# Probe1152A.net
KiCad netlist of a schematic drawn in Altium Designer
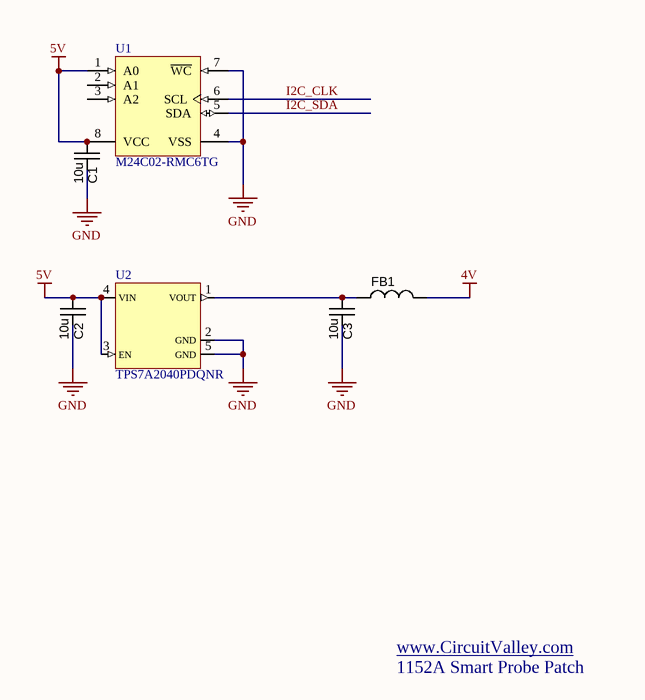
[diagram p0: Probe1152A.SchDoc]

(export (version "E")
  (design (tool "Eeschema 10.0.6"))
  (components
    (comp (ref "C1")
      (value "10u")
      (footprint "CAPC1608N")
      (description "Capacitor SMD Cer 560pF 5% 50V NP0 0603")
      (fields (field (name "Comment") "approved sub OK"))
      (libsource (lib "PBL - Capacitors") (part "CAPC_560p_0603_5%"))
    )
    (comp (ref "C2")
      (value "10u")
      (footprint "CAPC1608N")
      (description "Capacitor SMD Cer 560pF 5% 50V NP0 0603")
      (fields (field (name "Comment") "approved sub OK"))
      (libsource (lib "PBL - Capacitors") (part "CAPC_560p_0603_5%"))
    )
    (comp (ref "C3")
      (value "10u")
      (footprint "CAPC1608N")
      (description "Capacitor SMD Cer 560pF 5% 50V NP0 0603")
      (fields (field (name "Comment") "approved sub OK"))
      (libsource (lib "PBL - Capacitors") (part "CAPC_560p_0603_5%"))
    )
    (comp (ref "FB1")
      (value "~")
      (footprint "FBC2012N")
      (description "Ferrite bead 2.2K Ohm at 100 MHz 200mA 0805 SMD")
      (libsource (lib "PBL - Inductors") (part "FERRITE_2K2-100MHz_0805"))
    )
    (comp (ref "U1")
      (value "M24C02-RMC6TG")
      (footprint "DFN8_3x2_NO_PPAD")
      (libsource (lib "cvlib") (part "M24C02-RMC6TG"))
    )
    (comp (ref "U2")
      (value "TPS7A2040PDQNR")
      (footprint "X2SON-4")
      (description "LDO")
      (libsource (lib "cvlib") (part "TPS7A2040PDQNR"))
    )
  )
  (nets
    (net (code "1") (name "/I2C_CLK") (class "Default")
      (node (ref "U1") (pin "6") (pinfunction "SCL_6") (pintype "input"))
    )
    (net (code "2") (name "/I2C_SDA") (class "Default")
      (node (ref "U1") (pin "5") (pinfunction "SDA_5") (pintype "bidirectional"))
    )
    (net (code "3") (name "4V") (class "Default")
      (node (ref "FB1") (pin "2") (pinfunction "2_2") (pintype "passive"))
    )
    (net (code "4") (name "5V") (class "Default")
      (node (ref "C1") (pin "1") (pintype "passive"))
      (node (ref "C2") (pin "1") (pintype "passive"))
      (node (ref "U1") (pin "1") (pinfunction "A0_1") (pintype "input"))
      (node (ref "U1") (pin "8") (pinfunction "VCC_8") (pintype "power_in"))
      (node (ref "U2") (pin "3") (pinfunction "EN_3") (pintype "input"))
      (node (ref "U2") (pin "4") (pinfunction "VIN_4") (pintype "power_in"))
    )
    (net (code "5") (name "GND") (class "Default")
      (node (ref "C1") (pin "2") (pintype "passive"))
      (node (ref "C2") (pin "2") (pintype "passive"))
      (node (ref "C3") (pin "2") (pintype "passive"))
      (node (ref "U1") (pin "4") (pinfunction "VSS_4") (pintype "power_in"))
      (node (ref "U1") (pin "7") (pinfunction "~{WC}_7") (pintype "input"))
      (node (ref "U2") (pin "2") (pinfunction "GND_2") (pintype "power_in"))
      (node (ref "U2") (pin "5") (pinfunction "GND_5") (pintype "power_in"))
    )
    (net (code "6") (name "Net-(U2-VOUT)") (class "Default")
      (node (ref "C3") (pin "1") (pintype "passive"))
      (node (ref "FB1") (pin "1") (pinfunction "1_1") (pintype "passive"))
      (node (ref "U2") (pin "1") (pinfunction "VOUT_1") (pintype "output"))
    )
    (net (code "7") (name "unconnected-(U1-A1-Pad2)") (class "Default")
      (node (ref "U1") (pin "2") (pinfunction "A1_2") (pintype "input"))
    )
    (net (code "8") (name "unconnected-(U1-A2-Pad3)") (class "Default")
      (node (ref "U1") (pin "3") (pinfunction "A2_3") (pintype "input"))
    )
  )
)
